# P27_v2.net
KiCad netlist of a schematic drawn in EAGLE
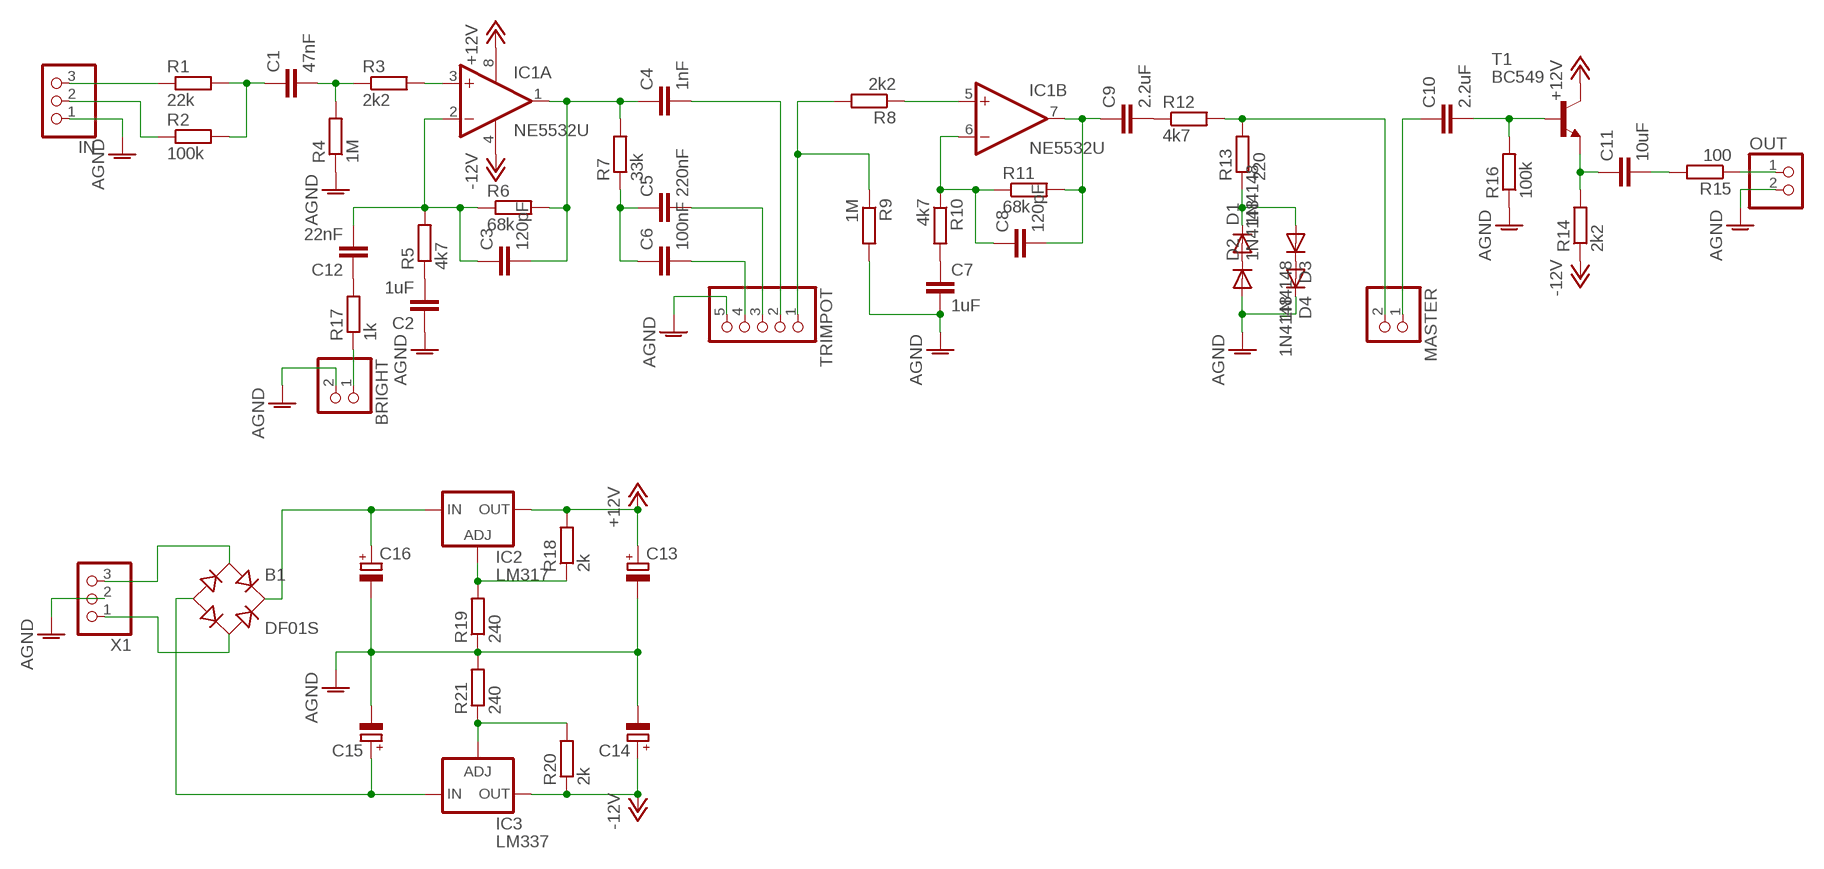
[diagram p0: schematic, sheet 1]

(export (version "E")
  (design (tool "Eeschema 10.0.6"))
  (components
    (comp (ref "B1")
      (value "DF01S")
      (footprint "eagle-import:DFS")
      (libsource (lib "eagle-import") (part "DFS01"))
    )
    (comp (ref "BRIGHT")
      (value "PINHD-1X2")
      (footprint "eagle-import:1X02")
      (libsource (lib "eagle-import") (part "PINHD-1X2"))
    )
    (comp (ref "C1")
      (value "47nF")
      (footprint "eagle-import:C0805K")
      (libsource (lib "eagle-import") (part "C-EUC0805K"))
    )
    (comp (ref "C2")
      (value "1uF")
      (footprint "eagle-import:C0805K")
      (libsource (lib "eagle-import") (part "C-EUC0805K"))
    )
    (comp (ref "C3")
      (value "120pF")
      (footprint "eagle-import:C0805K")
      (libsource (lib "eagle-import") (part "C-EUC0805K"))
    )
    (comp (ref "C4")
      (value "1nF")
      (footprint "eagle-import:C0805K")
      (libsource (lib "eagle-import") (part "C-EUC0805K"))
    )
    (comp (ref "C5")
      (value "220nF")
      (footprint "eagle-import:C0805K")
      (libsource (lib "eagle-import") (part "C-EUC0805K"))
    )
    (comp (ref "C6")
      (value "100nF")
      (footprint "eagle-import:C0805K")
      (libsource (lib "eagle-import") (part "C-EUC0805K"))
    )
    (comp (ref "C7")
      (value "1uF")
      (footprint "eagle-import:C0805K")
      (libsource (lib "eagle-import") (part "C-EUC0805K"))
    )
    (comp (ref "C8")
      (value "120pF")
      (footprint "eagle-import:C0805K")
      (libsource (lib "eagle-import") (part "C-EUC0805K"))
    )
    (comp (ref "C9")
      (value "2.2uF")
      (footprint "eagle-import:C1206")
      (libsource (lib "eagle-import") (part "C-EUC1206"))
    )
    (comp (ref "C10")
      (value "2.2uF")
      (footprint "eagle-import:C1206")
      (libsource (lib "eagle-import") (part "C-EUC1206"))
    )
    (comp (ref "C11")
      (value "10uF")
      (footprint "eagle-import:C1206")
      (libsource (lib "eagle-import") (part "C-EUC1206"))
    )
    (comp (ref "C12")
      (value "22nF")
      (footprint "eagle-import:C0805K")
      (libsource (lib "eagle-import") (part "C-EUC0805K"))
    )
    (comp (ref "C13")
      (value "CPOL-EUD")
      (footprint "eagle-import:PANASONIC_D")
      (libsource (lib "eagle-import") (part "CPOL-EUD"))
    )
    (comp (ref "C14")
      (value "CPOL-EUD")
      (footprint "eagle-import:PANASONIC_D")
      (libsource (lib "eagle-import") (part "CPOL-EUD"))
    )
    (comp (ref "C15")
      (value "CPOL-EUD")
      (footprint "eagle-import:PANASONIC_D")
      (libsource (lib "eagle-import") (part "CPOL-EUD"))
    )
    (comp (ref "C16")
      (value "CPOL-EUD")
      (footprint "eagle-import:PANASONIC_D")
      (libsource (lib "eagle-import") (part "CPOL-EUD"))
    )
    (comp (ref "D1")
      (value "1N4148")
      (footprint "eagle-import:D0805")
      (libsource (lib "eagle-import") (part "1N4148"))
    )
    (comp (ref "D2")
      (value "1N4148")
      (footprint "eagle-import:D0805")
      (libsource (lib "eagle-import") (part "1N4148"))
    )
    (comp (ref "D3")
      (value "1N4148")
      (footprint "eagle-import:D0805")
      (libsource (lib "eagle-import") (part "1N4148"))
    )
    (comp (ref "D4")
      (value "1N4148")
      (footprint "eagle-import:D0805")
      (libsource (lib "eagle-import") (part "1N4148"))
    )
    (comp (ref "IC1")
      (value "NE5532U")
      (footprint "eagle-import:SO08")
      (libsource (lib "eagle-import") (part "NE5532U"))
    )
    (comp (ref "IC2")
      (value "LM317")
      (footprint "eagle-import:SOT223")
      (libsource (lib "eagle-import") (part "LM317"))
    )
    (comp (ref "IC3")
      (value "LM337")
      (footprint "eagle-import:SOT223")
      (libsource (lib "eagle-import") (part "LM337"))
    )
    (comp (ref "IN")
      (value "PINHD-1X3180")
      (footprint "eagle-import:1X03")
      (libsource (lib "eagle-import") (part "PINHD-1X3180"))
    )
    (comp (ref "MASTER")
      (value "PINHD-1X2")
      (footprint "eagle-import:1X02")
      (libsource (lib "eagle-import") (part "PINHD-1X2"))
    )
    (comp (ref "OUT")
      (value "PINHD-1X2")
      (footprint "eagle-import:1X02")
      (libsource (lib "eagle-import") (part "PINHD-1X2"))
    )
    (comp (ref "R1")
      (value "22k")
      (footprint "eagle-import:R0805")
      (libsource (lib "eagle-import") (part "R-EU_0805"))
    )
    (comp (ref "R2")
      (value "100k")
      (footprint "eagle-import:R0805")
      (libsource (lib "eagle-import") (part "R-EU_0805"))
    )
    (comp (ref "R3")
      (value "2k2")
      (footprint "eagle-import:R0805")
      (libsource (lib "eagle-import") (part "R-EU_0805"))
    )
    (comp (ref "R4")
      (value "1M")
      (footprint "eagle-import:R0805")
      (libsource (lib "eagle-import") (part "R-EU_0805"))
    )
    (comp (ref "R5")
      (value "4k7")
      (footprint "eagle-import:R0805")
      (libsource (lib "eagle-import") (part "R-EU_0805"))
    )
    (comp (ref "R6")
      (value "68k")
      (footprint "eagle-import:R0805")
      (libsource (lib "eagle-import") (part "R-EU_0805"))
    )
    (comp (ref "R7")
      (value "33k")
      (footprint "eagle-import:R0805")
      (libsource (lib "eagle-import") (part "R-EU_0805"))
    )
    (comp (ref "R8")
      (value "2k2")
      (footprint "eagle-import:R0805")
      (libsource (lib "eagle-import") (part "R-EU_0805"))
    )
    (comp (ref "R9")
      (value "1M")
      (footprint "eagle-import:R0805")
      (libsource (lib "eagle-import") (part "R-EU_0805"))
    )
    (comp (ref "R10")
      (value "4k7")
      (footprint "eagle-import:R0805")
      (libsource (lib "eagle-import") (part "R-EU_0805"))
    )
    (comp (ref "R11")
      (value "68k")
      (footprint "eagle-import:R0805")
      (libsource (lib "eagle-import") (part "R-EU_0805"))
    )
    (comp (ref "R12")
      (value "4k7")
      (footprint "eagle-import:R0805")
      (libsource (lib "eagle-import") (part "R-EU_0805"))
    )
    (comp (ref "R13")
      (value "220")
      (footprint "eagle-import:R0805")
      (libsource (lib "eagle-import") (part "R-EU_0805"))
    )
    (comp (ref "R14")
      (value "2k2")
      (footprint "eagle-import:R0805")
      (libsource (lib "eagle-import") (part "R-EU_0805"))
    )
    (comp (ref "R15")
      (value "100")
      (footprint "eagle-import:R0805")
      (libsource (lib "eagle-import") (part "R-EU_0805"))
    )
    (comp (ref "R16")
      (value "100k")
      (footprint "eagle-import:R0805")
      (libsource (lib "eagle-import") (part "R-EU_0805"))
    )
    (comp (ref "R17")
      (value "1k")
      (footprint "eagle-import:R0805")
      (libsource (lib "eagle-import") (part "R-EU_0805"))
    )
    (comp (ref "R18")
      (value "2k")
      (footprint "eagle-import:R0805")
      (libsource (lib "eagle-import") (part "R-EU_0805"))
    )
    (comp (ref "R19")
      (value "240")
      (footprint "eagle-import:R0805")
      (libsource (lib "eagle-import") (part "R-EU_0805"))
    )
    (comp (ref "R20")
      (value "2k")
      (footprint "eagle-import:R0805")
      (libsource (lib "eagle-import") (part "R-EU_0805"))
    )
    (comp (ref "R21")
      (value "240")
      (footprint "eagle-import:R0805")
      (libsource (lib "eagle-import") (part "R-EU_0805"))
    )
    (comp (ref "T1")
      (value "BC549")
      (footprint "eagle-import:SOT23")
      (libsource (lib "eagle-import") (part "BC847"))
    )
    (comp (ref "TRIMPOT")
      (value "PINHD-1X5")
      (footprint "eagle-import:1X05")
      (libsource (lib "eagle-import") (part "PINHD-1X5"))
    )
    (comp (ref "X1")
      (value "W237-103")
      (footprint "eagle-import:W237-103")
      (libsource (lib "eagle-import") (part "W237-103"))
    )
  )
  (nets
    (net (code "1") (name "+12V") (class "Default")
      (node (ref "C13") (pin "+") (pinfunction "+_+") (pintype "passive"))
      (node (ref "IC1") (pin "8") (pinfunction "V+_8") (pintype "power_in"))
      (node (ref "IC2") (pin "2") (pinfunction "OUT_2") (pintype "passive"))
      (node (ref "IC2") (pin "4") (pinfunction "OUT_4") (pintype "passive"))
      (node (ref "R18") (pin "2") (pinfunction "2_2") (pintype "passive"))
      (node (ref "T1") (pin "3") (pinfunction "C_3") (pintype "passive"))
    )
    (net (code "2") (name "-12V") (class "Default")
      (node (ref "C14") (pin "+") (pinfunction "+_+") (pintype "passive"))
      (node (ref "IC1") (pin "4") (pinfunction "V-_4") (pintype "power_in"))
      (node (ref "IC3") (pin "3") (pinfunction "OUT_3") (pintype "passive"))
      (node (ref "R14") (pin "1") (pinfunction "1_1") (pintype "passive"))
      (node (ref "R20") (pin "1") (pinfunction "1_1") (pintype "passive"))
    )
    (net (code "3") (name "AGND") (class "Default")
      (node (ref "BRIGHT") (pin "2") (pinfunction "2_2") (pintype "passive"))
      (node (ref "C13") (pin "-") (pinfunction "-_-") (pintype "passive"))
      (node (ref "C14") (pin "-") (pinfunction "-_-") (pintype "passive"))
      (node (ref "C15") (pin "-") (pinfunction "-_-") (pintype "passive"))
      (node (ref "C16") (pin "-") (pinfunction "-_-") (pintype "passive"))
      (node (ref "C2") (pin "1") (pinfunction "1_1") (pintype "passive"))
      (node (ref "C7") (pin "2") (pinfunction "2_2") (pintype "passive"))
      (node (ref "D2") (pin "A") (pinfunction "A_A") (pintype "passive"))
      (node (ref "D4") (pin "K") (pinfunction "C_K") (pintype "passive"))
      (node (ref "IN") (pin "1") (pinfunction "1_1") (pintype "passive"))
      (node (ref "OUT") (pin "2") (pinfunction "2_2") (pintype "passive"))
      (node (ref "R16") (pin "1") (pinfunction "1_1") (pintype "passive"))
      (node (ref "R19") (pin "1") (pinfunction "1_1") (pintype "passive"))
      (node (ref "R21") (pin "2") (pinfunction "2_2") (pintype "passive"))
      (node (ref "R4") (pin "1") (pinfunction "1_1") (pintype "passive"))
      (node (ref "R9") (pin "2") (pinfunction "2_2") (pintype "passive"))
      (node (ref "TRIMPOT") (pin "5") (pinfunction "5_5") (pintype "passive"))
      (node (ref "X1") (pin "2") (pinfunction "2_2") (pintype "passive"))
    )
    (net (code "4") (name "Net-(B1-Pad-)") (class "Default")
      (node (ref "B1") (pin "-") (pinfunction "-_-") (pintype "passive"))
      (node (ref "C15") (pin "+") (pinfunction "+_+") (pintype "passive"))
      (node (ref "IC3") (pin "2") (pinfunction "IN_2") (pintype "input"))
      (node (ref "IC3") (pin "4") (pinfunction "IN_4") (pintype "input"))
    )
    (net (code "5") (name "Net-(B1-PadAC1)") (class "Default")
      (node (ref "B1") (pin "AC1") (pinfunction "AC1_AC1") (pintype "passive"))
      (node (ref "X1") (pin "3") (pinfunction "3_3") (pintype "passive"))
    )
    (net (code "6") (name "Net-(B1-PadAC2)") (class "Default")
      (node (ref "B1") (pin "AC2") (pinfunction "AC2_AC2") (pintype "passive"))
      (node (ref "X1") (pin "1") (pinfunction "1_1") (pintype "passive"))
    )
    (net (code "7") (name "Net-(BRIGHT-Pad1)") (class "Default")
      (node (ref "BRIGHT") (pin "1") (pinfunction "1_1") (pintype "passive"))
      (node (ref "R17") (pin "1") (pinfunction "1_1") (pintype "passive"))
    )
    (net (code "8") (name "Net-(C1-Pad1)") (class "Default")
      (node (ref "C1") (pin "1") (pinfunction "1_1") (pintype "passive"))
      (node (ref "R1") (pin "2") (pinfunction "2_2") (pintype "passive"))
      (node (ref "R2") (pin "2") (pinfunction "2_2") (pintype "passive"))
    )
    (net (code "9") (name "Net-(C1-Pad2)") (class "Default")
      (node (ref "C1") (pin "2") (pinfunction "2_2") (pintype "passive"))
      (node (ref "R3") (pin "1") (pinfunction "1_1") (pintype "passive"))
      (node (ref "R4") (pin "2") (pinfunction "2_2") (pintype "passive"))
    )
    (net (code "10") (name "Net-(C2-Pad2)") (class "Default")
      (node (ref "C2") (pin "2") (pinfunction "2_2") (pintype "passive"))
      (node (ref "R5") (pin "1") (pinfunction "1_1") (pintype "passive"))
    )
    (net (code "11") (name "Net-(C4-Pad2)") (class "Default")
      (node (ref "C4") (pin "2") (pinfunction "2_2") (pintype "passive"))
      (node (ref "TRIMPOT") (pin "2") (pinfunction "2_2") (pintype "passive"))
    )
    (net (code "12") (name "Net-(C5-Pad1)") (class "Default")
      (node (ref "C5") (pin "1") (pinfunction "1_1") (pintype "passive"))
      (node (ref "C6") (pin "1") (pinfunction "1_1") (pintype "passive"))
      (node (ref "R7") (pin "1") (pinfunction "1_1") (pintype "passive"))
    )
    (net (code "13") (name "Net-(C5-Pad2)") (class "Default")
      (node (ref "C5") (pin "2") (pinfunction "2_2") (pintype "passive"))
      (node (ref "TRIMPOT") (pin "3") (pinfunction "3_3") (pintype "passive"))
    )
    (net (code "14") (name "Net-(C6-Pad2)") (class "Default")
      (node (ref "C6") (pin "2") (pinfunction "2_2") (pintype "passive"))
      (node (ref "TRIMPOT") (pin "4") (pinfunction "4_4") (pintype "passive"))
    )
    (net (code "15") (name "Net-(C7-Pad1)") (class "Default")
      (node (ref "C7") (pin "1") (pinfunction "1_1") (pintype "passive"))
      (node (ref "R10") (pin "2") (pinfunction "2_2") (pintype "passive"))
    )
    (net (code "16") (name "Net-(C9-Pad2)") (class "Default")
      (node (ref "C9") (pin "2") (pinfunction "2_2") (pintype "passive"))
      (node (ref "R12") (pin "1") (pinfunction "1_1") (pintype "passive"))
    )
    (net (code "17") (name "Net-(C10-Pad1)") (class "Default")
      (node (ref "C10") (pin "1") (pinfunction "1_1") (pintype "passive"))
      (node (ref "MASTER") (pin "1") (pinfunction "1_1") (pintype "passive"))
    )
    (net (code "18") (name "Net-(C11-Pad2)") (class "Default")
      (node (ref "C11") (pin "2") (pinfunction "2_2") (pintype "passive"))
      (node (ref "R15") (pin "2") (pinfunction "2_2") (pintype "passive"))
    )
    (net (code "19") (name "Net-(C12-Pad1)") (class "Default")
      (node (ref "C12") (pin "1") (pinfunction "1_1") (pintype "passive"))
      (node (ref "R17") (pin "2") (pinfunction "2_2") (pintype "passive"))
    )
    (net (code "20") (name "Net-(D1-C)") (class "Default")
      (node (ref "D1") (pin "K") (pinfunction "C_K") (pintype "passive"))
      (node (ref "D3") (pin "A") (pinfunction "A_A") (pintype "passive"))
      (node (ref "R13") (pin "1") (pinfunction "1_1") (pintype "passive"))
    )
    (net (code "21") (name "Net-(D2-C)") (class "Default")
      (node (ref "D1") (pin "A") (pinfunction "A_A") (pintype "passive"))
      (node (ref "D2") (pin "K") (pinfunction "C_K") (pintype "passive"))
    )
    (net (code "22") (name "Net-(D3-C)") (class "Default")
      (node (ref "D3") (pin "K") (pinfunction "C_K") (pintype "passive"))
      (node (ref "D4") (pin "A") (pinfunction "A_A") (pintype "passive"))
    )
    (net (code "23") (name "Net-(IC1A-+IN)") (class "Default")
      (node (ref "IC1") (pin "3") (pinfunction "+IN_3") (pintype "input"))
      (node (ref "R3") (pin "2") (pinfunction "2_2") (pintype "passive"))
    )
    (net (code "24") (name "Net-(IC1A--IN)") (class "Default")
      (node (ref "C12") (pin "2") (pinfunction "2_2") (pintype "passive"))
      (node (ref "C3") (pin "1") (pinfunction "1_1") (pintype "passive"))
      (node (ref "IC1") (pin "2") (pinfunction "-IN_2") (pintype "input"))
      (node (ref "R5") (pin "2") (pinfunction "2_2") (pintype "passive"))
      (node (ref "R6") (pin "1") (pinfunction "1_1") (pintype "passive"))
    )
    (net (code "25") (name "Net-(IC1A-OUT)") (class "Default")
      (node (ref "C3") (pin "2") (pinfunction "2_2") (pintype "passive"))
      (node (ref "C4") (pin "1") (pinfunction "1_1") (pintype "passive"))
      (node (ref "IC1") (pin "1") (pinfunction "OUT_1") (pintype "output"))
      (node (ref "R6") (pin "2") (pinfunction "2_2") (pintype "passive"))
      (node (ref "R7") (pin "2") (pinfunction "2_2") (pintype "passive"))
    )
    (net (code "26") (name "Net-(IC1B-+IN)") (class "Default")
      (node (ref "IC1") (pin "5") (pinfunction "+IN_5") (pintype "input"))
      (node (ref "R8") (pin "1") (pinfunction "1_1") (pintype "passive"))
    )
    (net (code "27") (name "Net-(IC1B--IN)") (class "Default")
      (node (ref "C8") (pin "1") (pinfunction "1_1") (pintype "passive"))
      (node (ref "IC1") (pin "6") (pinfunction "-IN_6") (pintype "input"))
      (node (ref "R10") (pin "1") (pinfunction "1_1") (pintype "passive"))
      (node (ref "R11") (pin "1") (pinfunction "1_1") (pintype "passive"))
    )
    (net (code "28") (name "Net-(IC1B-OUT)") (class "Default")
      (node (ref "C8") (pin "2") (pinfunction "2_2") (pintype "passive"))
      (node (ref "C9") (pin "1") (pinfunction "1_1") (pintype "passive"))
      (node (ref "IC1") (pin "7") (pinfunction "OUT_7") (pintype "output"))
      (node (ref "R11") (pin "2") (pinfunction "2_2") (pintype "passive"))
    )
    (net (code "29") (name "Net-(IC2-ADJ)") (class "Default")
      (node (ref "IC2") (pin "1") (pinfunction "ADJ_1") (pintype "input"))
      (node (ref "R18") (pin "1") (pinfunction "1_1") (pintype "passive"))
      (node (ref "R19") (pin "2") (pinfunction "2_2") (pintype "passive"))
    )
    (net (code "30") (name "Net-(IC2-IN)") (class "Default")
      (node (ref "B1") (pin "+") (pinfunction "+_+") (pintype "passive"))
      (node (ref "C16") (pin "+") (pinfunction "+_+") (pintype "passive"))
      (node (ref "IC2") (pin "3") (pinfunction "IN_3") (pintype "input"))
    )
    (net (code "31") (name "Net-(IC3-ADJ)") (class "Default")
      (node (ref "IC3") (pin "1") (pinfunction "ADJ_1") (pintype "input"))
      (node (ref "R20") (pin "2") (pinfunction "2_2") (pintype "passive"))
      (node (ref "R21") (pin "1") (pinfunction "1_1") (pintype "passive"))
    )
    (net (code "32") (name "Net-(IN-Pad2)") (class "Default")
      (node (ref "IN") (pin "2") (pinfunction "2_2") (pintype "passive"))
      (node (ref "R2") (pin "1") (pinfunction "1_1") (pintype "passive"))
    )
    (net (code "33") (name "Net-(IN-Pad3)") (class "Default")
      (node (ref "IN") (pin "3") (pinfunction "3_3") (pintype "passive"))
      (node (ref "R1") (pin "1") (pinfunction "1_1") (pintype "passive"))
    )
    (net (code "34") (name "Net-(MASTER-Pad2)") (class "Default")
      (node (ref "MASTER") (pin "2") (pinfunction "2_2") (pintype "passive"))
      (node (ref "R12") (pin "2") (pinfunction "2_2") (pintype "passive"))
      (node (ref "R13") (pin "2") (pinfunction "2_2") (pintype "passive"))
    )
    (net (code "35") (name "Net-(OUT-Pad1)") (class "Default")
      (node (ref "OUT") (pin "1") (pinfunction "1_1") (pintype "passive"))
      (node (ref "R15") (pin "1") (pinfunction "1_1") (pintype "passive"))
    )
    (net (code "36") (name "Net-(R8-Pad2)") (class "Default")
      (node (ref "R8") (pin "2") (pinfunction "2_2") (pintype "passive"))
      (node (ref "R9") (pin "1") (pinfunction "1_1") (pintype "passive"))
      (node (ref "TRIMPOT") (pin "1") (pinfunction "1_1") (pintype "passive"))
    )
    (net (code "37") (name "Net-(T1-B)") (class "Default")
      (node (ref "C10") (pin "2") (pinfunction "2_2") (pintype "passive"))
      (node (ref "R16") (pin "2") (pinfunction "2_2") (pintype "passive"))
      (node (ref "T1") (pin "1") (pinfunction "B_1") (pintype "passive"))
    )
    (net (code "38") (name "Net-(T1-E)") (class "Default")
      (node (ref "C11") (pin "1") (pinfunction "1_1") (pintype "passive"))
      (node (ref "R14") (pin "2") (pinfunction "2_2") (pintype "passive"))
      (node (ref "T1") (pin "2") (pinfunction "E_2") (pintype "passive"))
    )
  )
)
